# ATSAMD10-XMINI_Target.net
KiCad netlist of a schematic drawn in Altium Designer
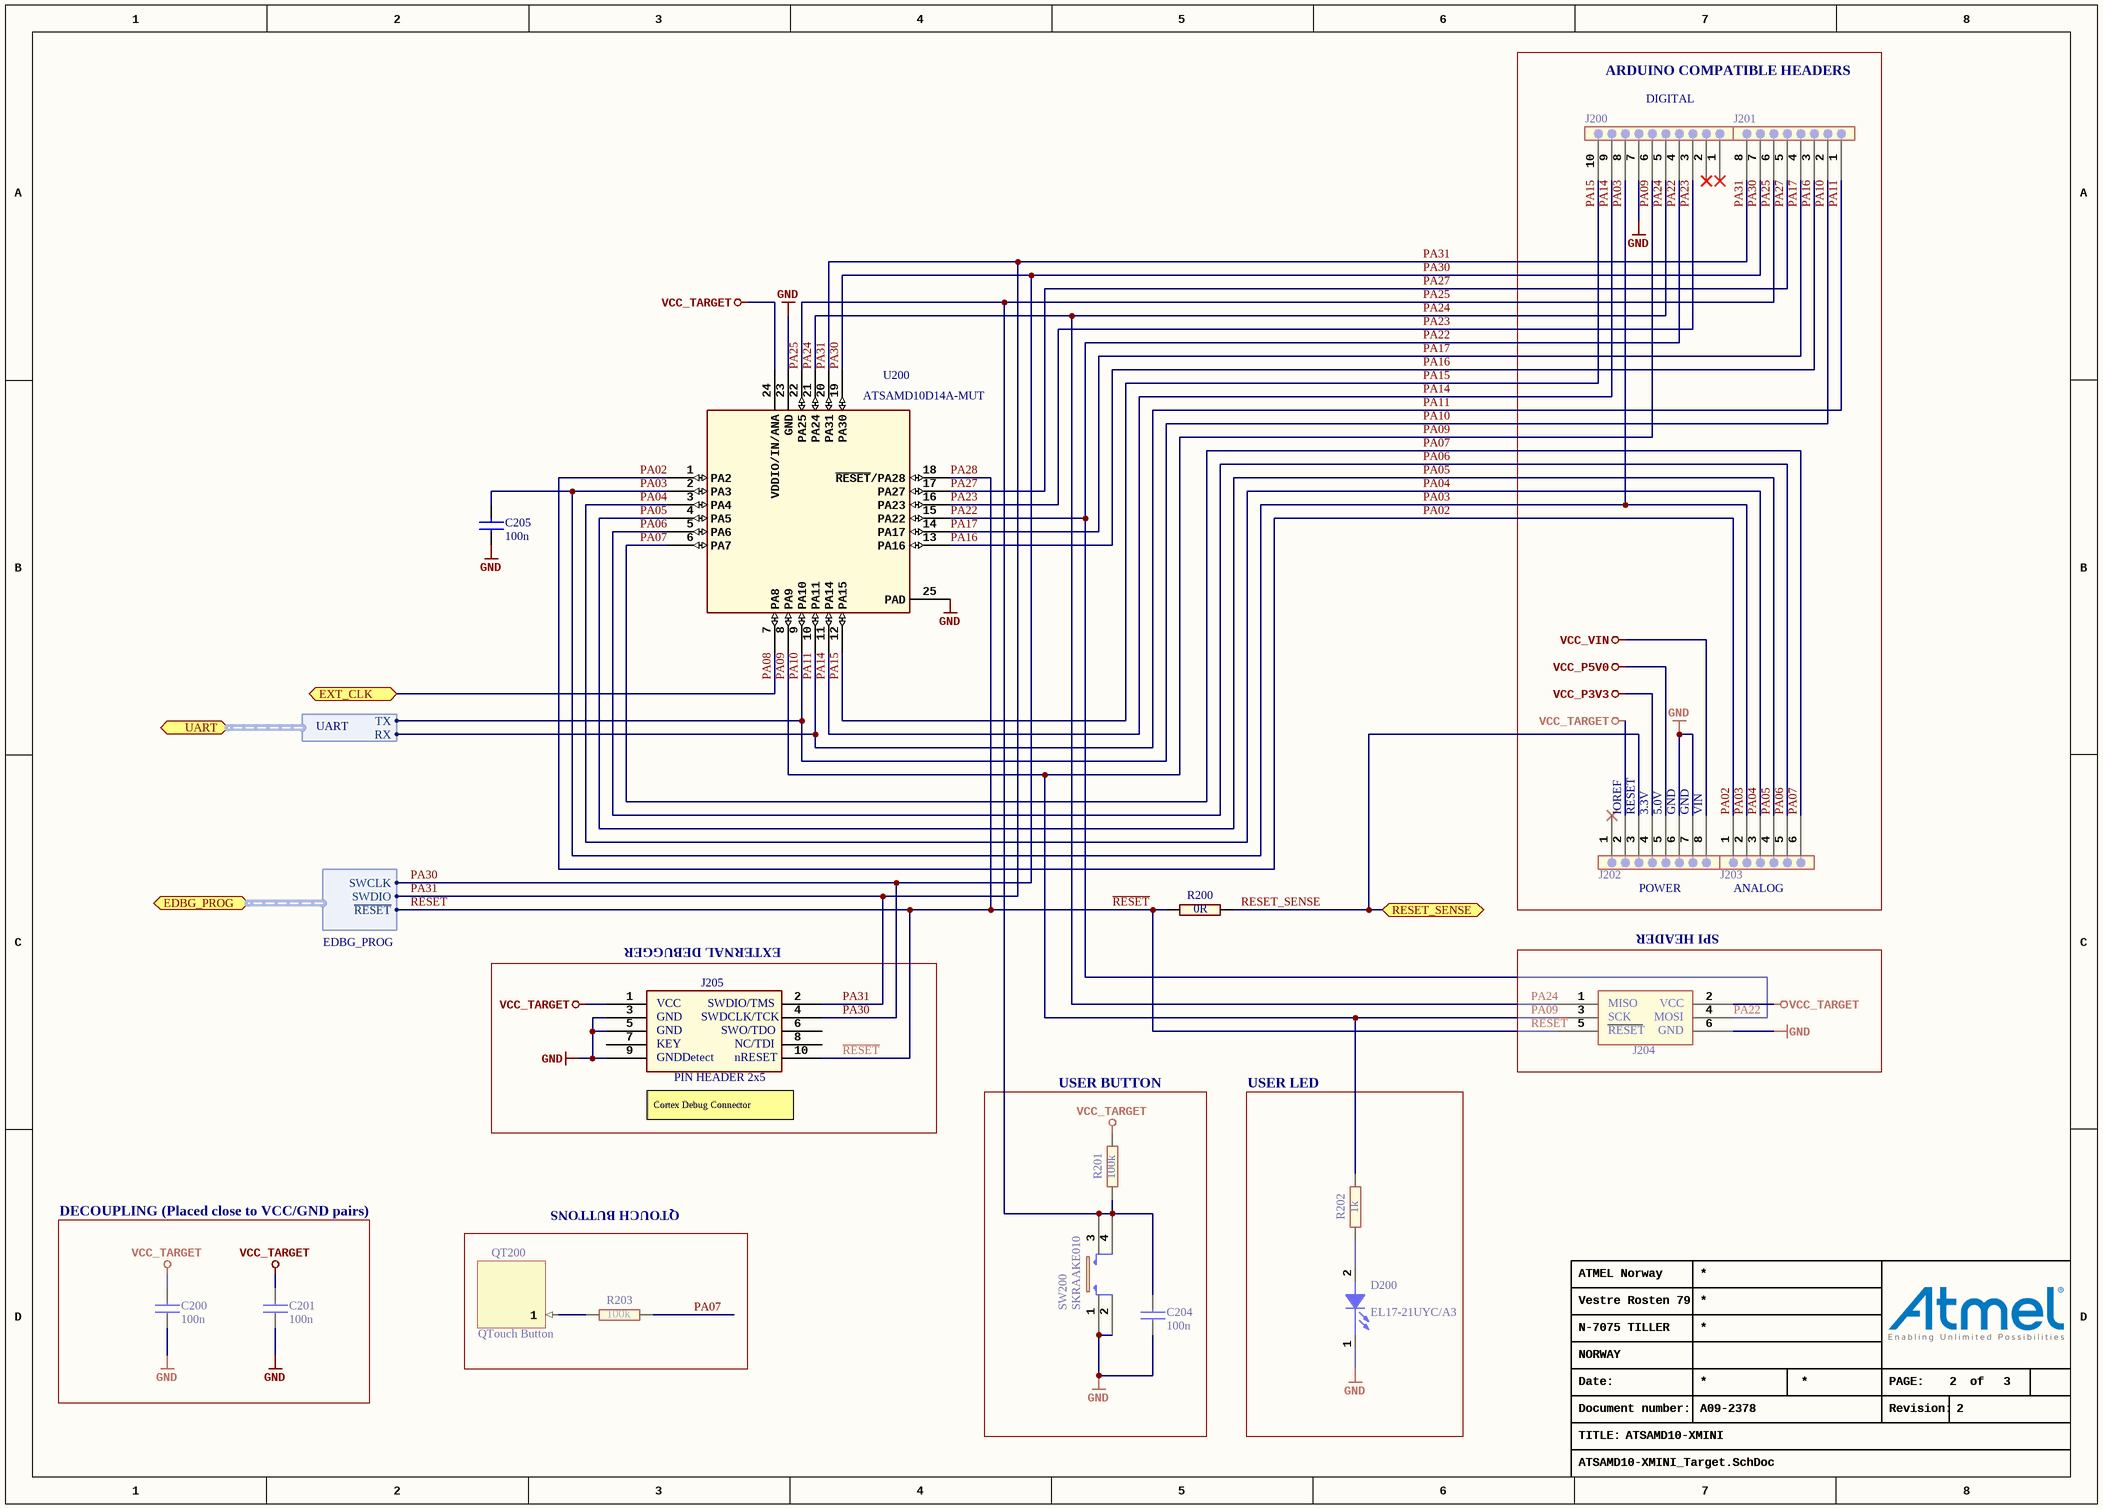
[diagram p0: ATSAMD10-XMINI_Target.SchDoc]

(export (version "E")
  (design (tool "Eeschema 10.0.6"))
  (components
    (comp (ref "C200")
      (value "100n")
      (footprint "AP1-00001")
      (description "Ceramic capacitor, SMD 0402, X7R, 16V, +/-10%")
      (fields (field (name "TOLERANCE") "16V, +/-10%") (field (name "MANUFACTURER") "Kemet"))
      (libsource (lib "AltiumDbLib") (part "CAP-NONPOL"))
    )
    (comp (ref "C201")
      (value "100n")
      (footprint "AP1-00001")
      (description "Ceramic capacitor, SMD 0402, X7R, 16V, +/-10%")
      (fields (field (name "TOLERANCE") "16V, +/-10%") (field (name "MANUFACTURER") "Kemet"))
      (libsource (lib "AltiumDbLib") (part "CAP-NONPOL"))
    )
    (comp (ref "C204")
      (value "100n")
      (footprint "AP1-00001")
      (description "Ceramic capacitor, SMD 0402, X7R, 16V, +/-10%")
      (fields (field (name "TOLERANCE") "16V, +/-10%") (field (name "MANUFACTURER") "Kemet"))
      (libsource (lib "AltiumDbLib") (part "CAP-NONPOL"))
    )
    (comp (ref "C205")
      (value "100n")
      (footprint "AP1-00001")
      (description "Ceramic capacitor, SMD 0402, X7R, 16V, +/-10%")
      (fields (field (name "TOLERANCE") "16V, +/-10%") (field (name "MANUFACTURER") "Kemet"))
      (libsource (lib "AltiumDbLib") (part "CAP-NONPOL"))
    )
    (comp (ref "D200")
      (value "EL17-21UYC/A3")
      (footprint "AP4-00013")
      (description "LED, Yellow, Wave length=591nm, SMD 0805, ±70°")
      (fields (field (name "MANUFACTURER") "Everlight") (field (name "MPN") "17-21UYC/S530-A3/TR8"))
      (libsource (lib "AltiumDbLib") (part "LED_12"))
    )
    (comp (ref "J200")
      (value "~")
      (footprint "AP8-00822")
      (description "1x10 receptacle pin header, low insertion force, 2.54mm pitch THM, Pin in Paste")
      (fields (field (name "MANUFACTURER") "SAMTEC") (field (name "MPN") "SSQ-110-21-F-S"))
      (libsource (lib "AltiumDbLib") (part "HEADER 1x10 FEMALE"))
    )
    (comp (ref "J201")
      (value "~")
      (footprint "AP8-00823")
      (description "1x8 receptacle pin header, low insertion force, 2.54mm pitch THM, Pin in Paste")
      (fields (field (name "MANUFACTURER") "SAMTEC") (field (name "MPN") "SSQ-108-21-F-S"))
      (libsource (lib "AltiumDbLib") (part "HEADER 1x8 FEMALE"))
    )
    (comp (ref "J202")
      (value "~")
      (footprint "AP8-00823")
      (description "1x8 receptacle pin header, low insertion force, 2.54mm pitch THM, Pin in Paste")
      (fields (field (name "MANUFACTURER") "SAMTEC") (field (name "MPN") "SSQ-108-21-F-S"))
      (libsource (lib "") (part "HEADER 1x8 FEMALE_1"))
    )
    (comp (ref "J203")
      (value "~")
      (footprint "AP8-00824")
      (description "1x6 receptacle pin header, low insertion force, 2.54mm pitch THM")
      (fields (field (name "MANUFACTURER") "SAMTEC") (field (name "MPN") "SSQ-106-21-F-S"))
      (libsource (lib "AltiumDbLib") (part "HEADER 1x6 FEMALE"))
    )
    (comp (ref "J204")
      (value "~")
      (footprint "AP8-00182")
      (description "2x3 pin header, 2.54 mm pitch, THM")
      (fields (field (name "MANUFACTURER") "SAMTEC") (field (name "MPN") "MTSW-103-08-L-D-276"))
      (libsource (lib "AltiumDbLib") (part "HEADER 2x3"))
    )
    (comp (ref "J205")
      (value "PIN HEADER 2x5")
      (footprint "AP8-00257")
      (description "2x5 pin header, 1.27mm pitch, THM")
      (fields (field (name "MANUFACTURER") "Garry") (field (name "MPN") "176-2-010-0-T-XS0-0730"))
      (libsource (lib "AltiumDbLib") (part "HEADER 2x5"))
    )
    (comp (ref "QT200") (value "QTouch Button") (libsource (lib "Atmel QTouch") (part "QTouchButton")))
    (comp (ref "R200")
      (value "0R")
      (footprint "AP2-00000")
      (description "RES 0.0 OHM 1/16W 0402 SMD")
      (fields (field (name "TOLERANCE") "1 %") (field (name "MANUFACTURER") "(n/a)"))
      (libsource (lib "") (part "R2_1"))
    )
    (comp (ref "R201")
      (value "100k")
      (footprint "AP2-00000")
      (description "Thick film resistor, SMD 0402, 1/16W, 1%")
      (fields (field (name "TOLERANCE") "1 %") (field (name "MANUFACTURER") "ASJ"))
      (libsource (lib "AltiumDbLib") (part "R2"))
    )
    (comp (ref "R202")
      (value "1k")
      (footprint "AP2-00000")
      (description "Thick film resistor, SMD 0402, 1/16W, 1%")
      (fields (field (name "TOLERANCE") "1 %") (field (name "MANUFACTURER") "ASJ"))
      (libsource (lib "AltiumDbLib") (part "R2"))
    )
    (comp (ref "R203")
      (value "100k")
      (footprint "AP2-00000")
      (description "Thick film resistor, SMD 0402, 1/16W, 1%")
      (fields (field (name "TOLERANCE") "1 %") (field (name "MANUFACTURER") "ASJ"))
      (libsource (lib "") (part "R2_1"))
    )
    (comp (ref "SW200")
      (value "SKRAAKE010")
      (footprint "AP8-00137")
      (description "6.2x6.2 mm SMD tact switch, same as A08-0091 but less force is needed")
      (fields (field (name "MANUFACTURER") "ALPS"))
      (libsource (lib "AltiumDbLib") (part "PUSHBUTTON1"))
    )
    (comp (ref "U200")
      (value "ATSAMD10D14A-MUT")
      (footprint "AP6-00371")
      (description "Atmel 32-bit RISC MCU")
      (fields (field (name "MANUFACTURER") "ATMEL"))
      (libsource (lib "AltiumDbLib") (part "SAMD10_QFN24"))
    )
  )
  (nets
    (net (code "3") (name "/PA02") (class "Default")
      (node (ref "J203") (pin "1") (pinfunction "1_1") (pintype "passive"))
      (node (ref "U200") (pin "1") (pinfunction "PA2_1") (pintype "bidirectional"))
    )
    (net (code "4") (name "/PA03") (class "Default")
      (node (ref "C205") (pin "2") (pinfunction "2_2") (pintype "passive"))
      (node (ref "J200") (pin "8") (pinfunction "8_8") (pintype "passive"))
      (node (ref "J203") (pin "2") (pinfunction "2_2") (pintype "passive"))
      (node (ref "U200") (pin "2") (pinfunction "PA3_2") (pintype "bidirectional"))
    )
    (net (code "5") (name "/PA04") (class "Default")
      (node (ref "J203") (pin "3") (pinfunction "3_3") (pintype "passive"))
      (node (ref "U200") (pin "3") (pinfunction "PA4_3") (pintype "bidirectional"))
    )
    (net (code "6") (name "/PA05") (class "Default")
      (node (ref "J203") (pin "4") (pinfunction "4_4") (pintype "passive"))
      (node (ref "U200") (pin "4") (pinfunction "PA5_4") (pintype "bidirectional"))
    )
    (net (code "7") (name "/PA06") (class "Default")
      (node (ref "J203") (pin "5") (pinfunction "5_5") (pintype "passive"))
      (node (ref "U200") (pin "5") (pinfunction "PA6_5") (pintype "bidirectional"))
    )
    (net (code "8") (name "/PA07") (class "Default")
      (node (ref "J203") (pin "6") (pinfunction "6_6") (pintype "passive"))
      (node (ref "R203") (pin "2") (pinfunction "2_2") (pintype "passive"))
      (node (ref "U200") (pin "6") (pinfunction "PA7_6") (pintype "bidirectional"))
    )
    (net (code "9") (name "/PA08") (class "Default")
      (node (ref "U200") (pin "7") (pinfunction "PA8_7") (pintype "bidirectional"))
    )
    (net (code "10") (name "/PA09") (class "Default")
      (node (ref "J200") (pin "6") (pinfunction "6_6") (pintype "passive"))
      (node (ref "J204") (pin "3") (pinfunction "3_3") (pintype "passive"))
      (node (ref "R202") (pin "2") (pinfunction "2_2") (pintype "passive"))
      (node (ref "U200") (pin "8") (pinfunction "PA9_8") (pintype "bidirectional"))
    )
    (net (code "11") (name "/PA10") (class "Default")
      (node (ref "J201") (pin "2") (pinfunction "2_2") (pintype "passive"))
      (node (ref "U200") (pin "9") (pinfunction "PA10_9") (pintype "bidirectional"))
    )
    (net (code "12") (name "/PA11") (class "Default")
      (node (ref "J201") (pin "1") (pinfunction "1_1") (pintype "passive"))
      (node (ref "U200") (pin "10") (pinfunction "PA11_10") (pintype "bidirectional"))
    )
    (net (code "13") (name "/PA14") (class "Default")
      (node (ref "J200") (pin "9") (pinfunction "9_9") (pintype "passive"))
      (node (ref "U200") (pin "11") (pinfunction "PA14_11") (pintype "bidirectional"))
    )
    (net (code "14") (name "/PA15") (class "Default")
      (node (ref "J200") (pin "10") (pinfunction "10_10") (pintype "passive"))
      (node (ref "U200") (pin "12") (pinfunction "PA15_12") (pintype "bidirectional"))
    )
    (net (code "15") (name "/PA16") (class "Default")
      (node (ref "J201") (pin "3") (pinfunction "3_3") (pintype "passive"))
      (node (ref "U200") (pin "13") (pinfunction "PA16_13") (pintype "bidirectional"))
    )
    (net (code "16") (name "/PA17") (class "Default")
      (node (ref "J201") (pin "4") (pinfunction "4_4") (pintype "passive"))
      (node (ref "U200") (pin "14") (pinfunction "PA17_14") (pintype "bidirectional"))
    )
    (net (code "17") (name "/PA22") (class "Default")
      (node (ref "J200") (pin "4") (pinfunction "4_4") (pintype "passive"))
      (node (ref "J204") (pin "4") (pinfunction "4_4") (pintype "passive"))
      (node (ref "U200") (pin "15") (pinfunction "PA22_15") (pintype "bidirectional"))
    )
    (net (code "18") (name "/PA23") (class "Default")
      (node (ref "J200") (pin "3") (pinfunction "3_3") (pintype "passive"))
      (node (ref "U200") (pin "16") (pinfunction "PA23_16") (pintype "bidirectional"))
    )
    (net (code "19") (name "/PA24") (class "Default")
      (node (ref "J200") (pin "5") (pinfunction "5_5") (pintype "passive"))
      (node (ref "J204") (pin "1") (pinfunction "1_1") (pintype "passive"))
      (node (ref "U200") (pin "21") (pinfunction "PA24_21") (pintype "bidirectional"))
    )
    (net (code "20") (name "/PA25") (class "Default")
      (node (ref "C204") (pin "2") (pinfunction "2_2") (pintype "passive"))
      (node (ref "J201") (pin "6") (pinfunction "6_6") (pintype "passive"))
      (node (ref "R201") (pin "1") (pinfunction "1_1") (pintype "passive"))
      (node (ref "SW200") (pin "3") (pinfunction "3_3") (pintype "passive"))
      (node (ref "SW200") (pin "4") (pinfunction "4_4") (pintype "passive"))
      (node (ref "U200") (pin "22") (pinfunction "PA25_22") (pintype "bidirectional"))
    )
    (net (code "21") (name "/PA27") (class "Default")
      (node (ref "J201") (pin "5") (pinfunction "5_5") (pintype "passive"))
      (node (ref "U200") (pin "17") (pinfunction "PA27_17") (pintype "bidirectional"))
    )
    (net (code "22") (name "/PA28") (class "Default")
      (node (ref "J204") (pin "5") (pinfunction "5_5") (pintype "passive"))
      (node (ref "J205") (pin "10") (pinfunction "10_10") (pintype "passive"))
      (node (ref "R200") (pin "1") (pinfunction "1_1") (pintype "passive"))
      (node (ref "U200") (pin "18") (pinfunction "~{RESET}/PA28_18") (pintype "bidirectional"))
    )
    (net (code "23") (name "/PA30") (class "Default")
      (node (ref "J201") (pin "7") (pinfunction "7_7") (pintype "passive"))
      (node (ref "J205") (pin "4") (pinfunction "4_4") (pintype "passive"))
      (node (ref "U200") (pin "19") (pinfunction "PA30_19") (pintype "bidirectional"))
    )
    (net (code "24") (name "/PA31") (class "Default")
      (node (ref "J201") (pin "8") (pinfunction "8_8") (pintype "passive"))
      (node (ref "J205") (pin "2") (pinfunction "2_2") (pintype "passive"))
      (node (ref "U200") (pin "20") (pinfunction "PA31_20") (pintype "bidirectional"))
    )
    (net (code "25") (name "/RESET_SENSE") (class "Default")
      (node (ref "J202") (pin "3") (pinfunction "3_3") (pintype "passive"))
      (node (ref "R200") (pin "2") (pinfunction "2_2") (pintype "passive"))
    )
    (net (code "28") (name "GND") (class "Default")
      (node (ref "C200") (pin "1") (pinfunction "1_1") (pintype "passive"))
      (node (ref "C201") (pin "1") (pinfunction "1_1") (pintype "passive"))
      (node (ref "C204") (pin "1") (pinfunction "1_1") (pintype "passive"))
      (node (ref "C205") (pin "1") (pinfunction "1_1") (pintype "passive"))
      (node (ref "D200") (pin "1") (pinfunction "CATHODE_1") (pintype "passive"))
      (node (ref "J200") (pin "7") (pinfunction "7_7") (pintype "passive"))
      (node (ref "J202") (pin "6") (pinfunction "6_6") (pintype "passive"))
      (node (ref "J202") (pin "7") (pinfunction "7_7") (pintype "passive"))
      (node (ref "J204") (pin "6") (pinfunction "6_6") (pintype "passive"))
      (node (ref "J205") (pin "3") (pinfunction "3_3") (pintype "passive"))
      (node (ref "J205") (pin "5") (pinfunction "5_5") (pintype "passive"))
      (node (ref "J205") (pin "9") (pinfunction "9_9") (pintype "passive"))
      (node (ref "SW200") (pin "1") (pinfunction "1_1") (pintype "passive"))
      (node (ref "SW200") (pin "2") (pinfunction "2_2") (pintype "passive"))
      (node (ref "U200") (pin "23") (pinfunction "GND_23") (pintype "power_in"))
      (node (ref "U200") (pin "25") (pinfunction "PAD_25") (pintype "passive"))
    )
    (net (code "29") (name "Net-(D200-ANODE)") (class "Default")
      (node (ref "D200") (pin "2") (pinfunction "ANODE_2") (pintype "passive"))
      (node (ref "R202") (pin "1") (pinfunction "1_1") (pintype "passive"))
    )
    (net (code "30") (name "Net-(QT200-Pad1)") (class "Default")
      (node (ref "QT200") (pin "1") (pinfunction "1_1") (pintype "input"))
      (node (ref "R203") (pin "1") (pinfunction "1_1") (pintype "passive"))
    )
    (net (code "31") (name "VCC_P3V3") (class "Default")
      (node (ref "J202") (pin "4") (pinfunction "4_4") (pintype "passive"))
    )
    (net (code "32") (name "VCC_P5V0") (class "Default")
      (node (ref "J202") (pin "5") (pinfunction "5_5") (pintype "passive"))
    )
    (net (code "33") (name "VCC_TARGET") (class "Default")
      (node (ref "C200") (pin "2") (pinfunction "2_2") (pintype "passive"))
      (node (ref "C201") (pin "2") (pinfunction "2_2") (pintype "passive"))
      (node (ref "J202") (pin "2") (pinfunction "2_2") (pintype "passive"))
      (node (ref "J204") (pin "2") (pinfunction "2_2") (pintype "passive"))
      (node (ref "J205") (pin "1") (pinfunction "1_1") (pintype "passive"))
      (node (ref "R201") (pin "2") (pinfunction "2_2") (pintype "passive"))
      (node (ref "U200") (pin "24") (pinfunction "VDDIO/IN/ANA_24") (pintype "power_in"))
    )
    (net (code "34") (name "VCC_VIN") (class "Default")
      (node (ref "J202") (pin "8") (pinfunction "8_8") (pintype "passive"))
    )
    (net (code "35") (name "unconnected-(J200-Pad1)") (class "Default")
      (node (ref "J200") (pin "1") (pinfunction "1_1") (pintype "passive+no_connect"))
    )
    (net (code "36") (name "unconnected-(J200-Pad2)") (class "Default")
      (node (ref "J200") (pin "2") (pinfunction "2_2") (pintype "passive+no_connect"))
    )
    (net (code "37") (name "unconnected-(J202-Pad1)") (class "Default")
      (node (ref "J202") (pin "1") (pinfunction "1_1") (pintype "passive+no_connect"))
    )
    (net (code "38") (name "unconnected-(J205-Pad6)") (class "Default")
      (node (ref "J205") (pin "6") (pinfunction "6_6") (pintype "passive"))
    )
    (net (code "39") (name "unconnected-(J205-Pad7)") (class "Default")
      (node (ref "J205") (pin "7") (pinfunction "7_7") (pintype "passive"))
    )
    (net (code "40") (name "unconnected-(J205-Pad8)") (class "Default")
      (node (ref "J205") (pin "8") (pinfunction "8_8") (pintype "passive"))
    )
  )
)
